# RP2350.net
KiCad netlist of a schematic drawn in Altium Designer
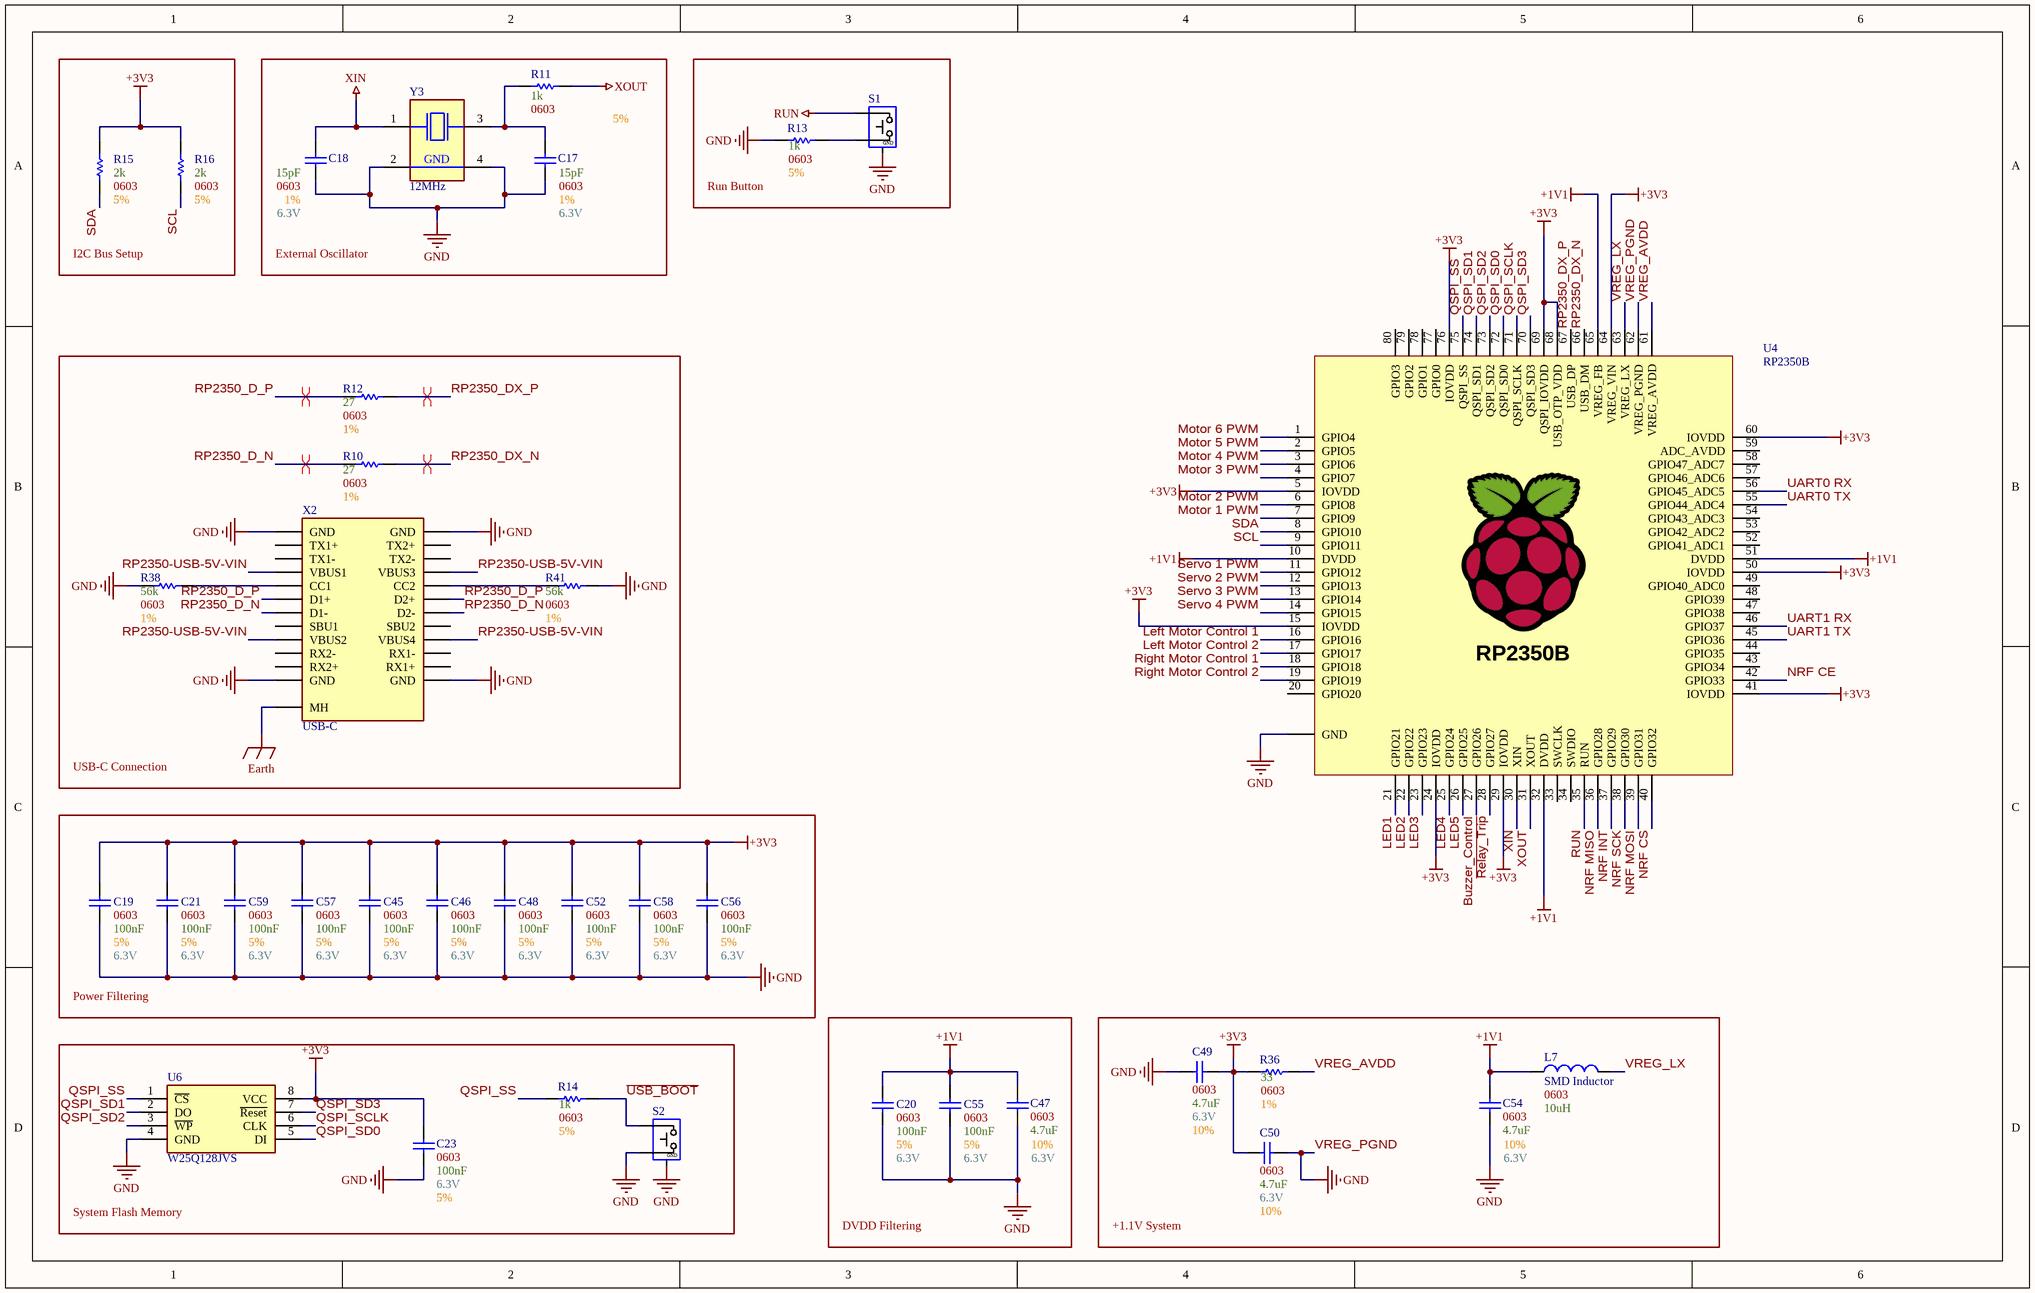
[diagram p0: RP2350.SchDoc]

(export (version "E")
  (design (tool "Eeschema 10.0.6"))
  (components
    (comp (ref "C17")
      (value "[Cap] SMD Nonpolarized")
      (footprint "[Cap] SMD 0603")
      (fields
        (field (name "SIZE PACKAGE") "0603")
        (field (name "CAPACITANCE") "15pF")
        (field (name "VOLTAGE") "6.3V")
        (field (name "TOLERANCE") "1%")
      )
      (libsource (lib "RADM Components") (part "[Cap] SMD Nonpolarized"))
    )
    (comp (ref "C18")
      (value "[Cap] SMD Nonpolarized")
      (footprint "[Cap] SMD 0603")
      (fields
        (field (name "SIZE PACKAGE") "0603")
        (field (name "CAPACITANCE") "15pF")
        (field (name "VOLTAGE") "6.3V")
        (field (name "TOLERANCE") "1%")
      )
      (libsource (lib "RADM Components") (part "[Cap] SMD Nonpolarized"))
    )
    (comp (ref "C19")
      (value "[Cap] SMD Nonpolarized")
      (footprint "[Cap] SMD 0603")
      (fields
        (field (name "SIZE PACKAGE") "0603")
        (field (name "CAPACITANCE") "100nF")
        (field (name "VOLTAGE") "6.3V")
        (field (name "TOLERANCE") "5%")
      )
      (libsource (lib "RADM Components") (part "[Cap] SMD Nonpolarized"))
    )
    (comp (ref "C20")
      (value "[Cap] SMD Nonpolarized")
      (footprint "[Cap] SMD 0603")
      (fields
        (field (name "SIZE PACKAGE") "0603")
        (field (name "CAPACITANCE") "100nF")
        (field (name "VOLTAGE") "6.3V")
        (field (name "TOLERANCE") "5%")
      )
      (libsource (lib "RADM Components") (part "[Cap] SMD Nonpolarized"))
    )
    (comp (ref "C21")
      (value "[Cap] SMD Nonpolarized")
      (footprint "[Cap] SMD 0603")
      (fields
        (field (name "SIZE PACKAGE") "0603")
        (field (name "CAPACITANCE") "100nF")
        (field (name "VOLTAGE") "6.3V")
        (field (name "TOLERANCE") "5%")
      )
      (libsource (lib "RADM Components") (part "[Cap] SMD Nonpolarized"))
    )
    (comp (ref "C23")
      (value "[Cap] SMD Nonpolarized")
      (footprint "[Cap] SMD 0603")
      (fields
        (field (name "SIZE PACKAGE") "0603")
        (field (name "CAPACITANCE") "100nF")
        (field (name "VOLTAGE") "6.3V")
        (field (name "TOLERANCE") "5%")
      )
      (libsource (lib "RADM Components") (part "[Cap] SMD Nonpolarized"))
    )
    (comp (ref "C45")
      (value "[Cap] SMD Nonpolarized")
      (footprint "[Cap] SMD 0603")
      (fields
        (field (name "SIZE PACKAGE") "0603")
        (field (name "CAPACITANCE") "100nF")
        (field (name "VOLTAGE") "6.3V")
        (field (name "TOLERANCE") "5%")
      )
      (libsource (lib "RADM Components") (part "[Cap] SMD Nonpolarized"))
    )
    (comp (ref "C46")
      (value "[Cap] SMD Nonpolarized")
      (footprint "[Cap] SMD 0603")
      (fields
        (field (name "SIZE PACKAGE") "0603")
        (field (name "CAPACITANCE") "100nF")
        (field (name "VOLTAGE") "6.3V")
        (field (name "TOLERANCE") "5%")
      )
      (libsource (lib "RADM Components") (part "[Cap] SMD Nonpolarized"))
    )
    (comp (ref "C47")
      (value "[Cap] SMD Nonpolarized")
      (footprint "[Cap] SMD 0603")
      (fields
        (field (name "SIZE PACKAGE") "0603")
        (field (name "CAPACITANCE") "4.7uF")
        (field (name "VOLTAGE") "6.3V")
        (field (name "TOLERANCE") "10%")
      )
      (libsource (lib "RADM Components") (part "[Cap] SMD Nonpolarized"))
    )
    (comp (ref "C48")
      (value "[Cap] SMD Nonpolarized")
      (footprint "[Cap] SMD 0603")
      (fields
        (field (name "SIZE PACKAGE") "0603")
        (field (name "CAPACITANCE") "100nF")
        (field (name "VOLTAGE") "6.3V")
        (field (name "TOLERANCE") "5%")
      )
      (libsource (lib "RADM Components") (part "[Cap] SMD Nonpolarized"))
    )
    (comp (ref "C49")
      (value "[Cap] SMD Nonpolarized")
      (footprint "[Cap] SMD 0603")
      (fields
        (field (name "SIZE PACKAGE") "0603")
        (field (name "CAPACITANCE") "4.7uF")
        (field (name "VOLTAGE") "6.3V")
        (field (name "TOLERANCE") "10%")
      )
      (libsource (lib "RADM Components") (part "[Cap] SMD Nonpolarized"))
    )
    (comp (ref "C50")
      (value "[Cap] SMD Nonpolarized")
      (footprint "[Cap] SMD 0603")
      (fields
        (field (name "SIZE PACKAGE") "0603")
        (field (name "CAPACITANCE") "4.7uF")
        (field (name "VOLTAGE") "6.3V")
        (field (name "TOLERANCE") "10%")
      )
      (libsource (lib "RADM Components") (part "[Cap] SMD Nonpolarized"))
    )
    (comp (ref "C52")
      (value "[Cap] SMD Nonpolarized")
      (footprint "[Cap] SMD 0603")
      (fields
        (field (name "SIZE PACKAGE") "0603")
        (field (name "CAPACITANCE") "100nF")
        (field (name "VOLTAGE") "6.3V")
        (field (name "TOLERANCE") "5%")
      )
      (libsource (lib "RADM Components") (part "[Cap] SMD Nonpolarized"))
    )
    (comp (ref "C54")
      (value "[Cap] SMD Nonpolarized")
      (footprint "[Cap] SMD 0603")
      (fields
        (field (name "SIZE PACKAGE") "0603")
        (field (name "CAPACITANCE") "4.7uF")
        (field (name "VOLTAGE") "6.3V")
        (field (name "TOLERANCE") "10%")
      )
      (libsource (lib "RADM Components") (part "[Cap] SMD Nonpolarized"))
    )
    (comp (ref "C55")
      (value "[Cap] SMD Nonpolarized")
      (footprint "[Cap] SMD 0603")
      (fields
        (field (name "SIZE PACKAGE") "0603")
        (field (name "CAPACITANCE") "100nF")
        (field (name "VOLTAGE") "6.3V")
        (field (name "TOLERANCE") "5%")
      )
      (libsource (lib "RADM Components") (part "[Cap] SMD Nonpolarized"))
    )
    (comp (ref "C56")
      (value "[Cap] SMD Nonpolarized")
      (footprint "[Cap] SMD 0603")
      (fields
        (field (name "SIZE PACKAGE") "0603")
        (field (name "CAPACITANCE") "100nF")
        (field (name "VOLTAGE") "6.3V")
        (field (name "TOLERANCE") "5%")
      )
      (libsource (lib "RADM Components") (part "[Cap] SMD Nonpolarized"))
    )
    (comp (ref "C57")
      (value "[Cap] SMD Nonpolarized")
      (footprint "[Cap] SMD 0603")
      (fields
        (field (name "SIZE PACKAGE") "0603")
        (field (name "CAPACITANCE") "100nF")
        (field (name "VOLTAGE") "6.3V")
        (field (name "TOLERANCE") "5%")
      )
      (libsource (lib "RADM Components") (part "[Cap] SMD Nonpolarized"))
    )
    (comp (ref "C58")
      (value "[Cap] SMD Nonpolarized")
      (footprint "[Cap] SMD 0603")
      (fields
        (field (name "SIZE PACKAGE") "0603")
        (field (name "CAPACITANCE") "100nF")
        (field (name "VOLTAGE") "6.3V")
        (field (name "TOLERANCE") "5%")
      )
      (libsource (lib "RADM Components") (part "[Cap] SMD Nonpolarized"))
    )
    (comp (ref "C59")
      (value "[Cap] SMD Nonpolarized")
      (footprint "[Cap] SMD 0603")
      (fields
        (field (name "SIZE PACKAGE") "0603")
        (field (name "CAPACITANCE") "100nF")
        (field (name "VOLTAGE") "6.3V")
        (field (name "TOLERANCE") "5%")
      )
      (libsource (lib "RADM Components") (part "[Cap] SMD Nonpolarized"))
    )
    (comp (ref "L7")
      (value "SMD Inductor")
      (footprint "[Inductor] SMD 0603")
      (fields (field (name "SIZE PACKAGE") "0603") (field (name "INDUCTANCE") "10uH"))
      (libsource (lib "RADM Components") (part "[Inductor] SMD Inductor"))
    )
    (comp (ref "R10")
      (value "[Res] SMD Resistor")
      (footprint "[Res] SMD 0603")
      (description "Generic")
      (fields
        (field (name "TOLERANCE") "1%")
        (field (name "RESISTANCE") "27")
        (field (name "SIZE PACKAGE") "0603")
      )
      (libsource (lib "RADM Components") (part "[Res] SMD Resistor"))
    )
    (comp (ref "R11")
      (value "[Res] SMD Resistor")
      (footprint "[Res] SMD 0603")
      (description "Generic")
      (fields
        (field (name "RESISTANCE") "1k")
        (field (name "SIZE PACKAGE") "0603")
        (field (name "TOLERANCE") "5%")
      )
      (libsource (lib "RADM Components") (part "[Res] SMD Resistor"))
    )
    (comp (ref "R12")
      (value "[Res] SMD Resistor")
      (footprint "[Res] SMD 0603")
      (description "Generic")
      (fields
        (field (name "TOLERANCE") "1%")
        (field (name "RESISTANCE") "27")
        (field (name "SIZE PACKAGE") "0603")
      )
      (libsource (lib "RADM Components") (part "[Res] SMD Resistor"))
    )
    (comp (ref "R13")
      (value "[Res] SMD Resistor")
      (footprint "[Res] SMD 0603")
      (description "Generic")
      (fields
        (field (name "RESISTANCE") "1k")
        (field (name "SIZE PACKAGE") "0603")
        (field (name "TOLERANCE") "5%")
      )
      (libsource (lib "RADM Components") (part "[Res] SMD Resistor"))
    )
    (comp (ref "R14")
      (value "[Res] SMD Resistor")
      (footprint "[Res] SMD 0603")
      (description "Generic")
      (fields
        (field (name "RESISTANCE") "1k")
        (field (name "SIZE PACKAGE") "0603")
        (field (name "TOLERANCE") "5%")
      )
      (libsource (lib "RADM Components") (part "[Res] SMD Resistor"))
    )
    (comp (ref "R15")
      (value "[Res] SMD Resistor")
      (footprint "[Res] SMD 0603")
      (description "Generic")
      (fields
        (field (name "RESISTANCE") "2k")
        (field (name "SIZE PACKAGE") "0603")
        (field (name "TOLERANCE") "5%")
      )
      (libsource (lib "RADM Components") (part "[Res] SMD Resistor"))
    )
    (comp (ref "R16")
      (value "[Res] SMD Resistor")
      (footprint "[Res] SMD 0603")
      (description "Generic")
      (fields
        (field (name "RESISTANCE") "2k")
        (field (name "SIZE PACKAGE") "0603")
        (field (name "TOLERANCE") "5%")
      )
      (libsource (lib "RADM Components") (part "[Res] SMD Resistor"))
    )
    (comp (ref "R36")
      (value "[Res] SMD Resistor")
      (footprint "[Res] SMD 0603")
      (description "Generic")
      (fields
        (field (name "RESISTANCE") "33")
        (field (name "SIZE PACKAGE") "0603")
        (field (name "TOLERANCE") "1%")
      )
      (libsource (lib "RADM Components") (part "[Res] SMD Resistor"))
    )
    (comp (ref "R38")
      (value "[Res] SMD Resistor")
      (footprint "[Res] SMD 0603")
      (description "Generic")
      (fields
        (field (name "TOLERANCE") "1%")
        (field (name "RESISTANCE") "56k")
        (field (name "SIZE PACKAGE") "0603")
      )
      (libsource (lib "RADM Components") (part "[Res] SMD Resistor"))
    )
    (comp (ref "R41")
      (value "[Res] SMD Resistor")
      (footprint "[Res] SMD 0603")
      (description "Generic")
      (fields
        (field (name "TOLERANCE") "1%")
        (field (name "RESISTANCE") "56k")
        (field (name "SIZE PACKAGE") "0603")
      )
      (libsource (lib "RADM Components") (part "[Res] SMD Resistor"))
    )
    (comp (ref "S1")
      (value "[Switch] Pushbutton SMD")
      (footprint "[Switch] Pushbutton SMD 2")
      (libsource (lib "RADM Components") (part "[Switch] Pushbutton SMD"))
    )
    (comp (ref "S2")
      (value "[Switch] Pushbutton SMD")
      (footprint "[Switch] Pushbutton SMD 2")
      (libsource (lib "RADM Components") (part "[Switch] Pushbutton SMD"))
    )
    (comp (ref "U4")
      (value "RP2350B")
      (footprint "[MCU] RP2350B")
      (description "QFN-80 Package")
      (libsource (lib "RADM Components") (part "[MCU] RP2350B"))
    )
    (comp (ref "U6")
      (value "W25Q128JVS")
      (footprint "[Mem] 16Mb Flash Memory")
      (description "W25Q128JVSIQ TR")
      (libsource (lib "RADM Components") (part "[Mem] 16Mb Flash Memory"))
    )
    (comp (ref "X2")
      (value "USB-C")
      (footprint "[Port] USB-C")
      (libsource (lib "RADM Connectors") (part "[Port] USB Type-C"))
    )
    (comp (ref "Y3")
      (value "12MHz")
      (footprint "[XTAL] SMD 12MHz")
      (description "815-ABM8-272-T3")
      (libsource (lib "RADM Components") (part "[XTAL] SMD 12MHz"))
    )
  )
  (nets
    (net (code "1") (name "+1V1") (class "Default")
      (node (ref "C20") (pin "2") (pinfunction "2_2") (pintype "passive"))
      (node (ref "C47") (pin "2") (pinfunction "2_2") (pintype "passive"))
      (node (ref "C54") (pin "2") (pinfunction "2_2") (pintype "passive"))
      (node (ref "C55") (pin "2") (pinfunction "2_2") (pintype "passive"))
      (node (ref "L7") (pin "1") (pinfunction "1_1") (pintype "passive"))
      (node (ref "U4") (pin "10") (pinfunction "DVDD_10") (pintype "passive"))
      (node (ref "U4") (pin "32") (pinfunction "DVDD_32") (pintype "passive"))
      (node (ref "U4") (pin "51") (pinfunction "DVDD_51") (pintype "passive"))
      (node (ref "U4") (pin "65") (pinfunction "VREG_FB_65") (pintype "passive"))
    )
    (net (code "2") (name "+3V3") (class "Default")
      (node (ref "C19") (pin "2") (pinfunction "2_2") (pintype "passive"))
      (node (ref "C21") (pin "2") (pinfunction "2_2") (pintype "passive"))
      (node (ref "C23") (pin "1") (pinfunction "1_1") (pintype "passive"))
      (node (ref "C45") (pin "2") (pinfunction "2_2") (pintype "passive"))
      (node (ref "C46") (pin "2") (pinfunction "2_2") (pintype "passive"))
      (node (ref "C48") (pin "2") (pinfunction "2_2") (pintype "passive"))
      (node (ref "C49") (pin "1") (pinfunction "1_1") (pintype "passive"))
      (node (ref "C50") (pin "2") (pinfunction "2_2") (pintype "passive"))
      (node (ref "C52") (pin "2") (pinfunction "2_2") (pintype "passive"))
      (node (ref "C56") (pin "2") (pinfunction "2_2") (pintype "passive"))
      (node (ref "C57") (pin "2") (pinfunction "2_2") (pintype "passive"))
      (node (ref "C58") (pin "2") (pinfunction "2_2") (pintype "passive"))
      (node (ref "C59") (pin "2") (pinfunction "2_2") (pintype "passive"))
      (node (ref "R15") (pin "2") (pinfunction "2_2") (pintype "passive"))
      (node (ref "R16") (pin "2") (pinfunction "2_2") (pintype "passive"))
      (node (ref "R36") (pin "2") (pinfunction "2_2") (pintype "passive"))
      (node (ref "U4") (pin "15") (pinfunction "IOVDD_15") (pintype "passive"))
      (node (ref "U4") (pin "24") (pinfunction "IOVDD_24") (pintype "passive"))
      (node (ref "U4") (pin "29") (pinfunction "IOVDD_29") (pintype "passive"))
      (node (ref "U4") (pin "41") (pinfunction "IOVDD_41") (pintype "passive"))
      (node (ref "U4") (pin "5") (pinfunction "IOVDD_5") (pintype "passive"))
      (node (ref "U4") (pin "50") (pinfunction "IOVDD_50") (pintype "passive"))
      (node (ref "U4") (pin "60") (pinfunction "IOVDD_60") (pintype "passive"))
      (node (ref "U4") (pin "64") (pinfunction "VREG_VIN_64") (pintype "passive"))
      (node (ref "U4") (pin "68") (pinfunction "USB_OTP_VDD_68") (pintype "passive"))
      (node (ref "U4") (pin "69") (pinfunction "QSPI_IOVDD_69") (pintype "passive"))
      (node (ref "U4") (pin "76") (pinfunction "IOVDD_76") (pintype "passive"))
      (node (ref "U6") (pin "8") (pinfunction "VCC_8") (pintype "passive"))
    )
    (net (code "3") (name "/Buzzer_Control") (class "Default")
      (node (ref "U4") (pin "27") (pinfunction "GPIO26_27") (pintype "passive"))
    )
    (net (code "4") (name "/LED1") (class "Default")
      (node (ref "U4") (pin "21") (pinfunction "GPIO21_21") (pintype "passive"))
    )
    (net (code "5") (name "/LED2") (class "Default")
      (node (ref "U4") (pin "22") (pinfunction "GPIO22_22") (pintype "passive"))
    )
    (net (code "6") (name "/LED3") (class "Default")
      (node (ref "U4") (pin "23") (pinfunction "GPIO23_23") (pintype "passive"))
    )
    (net (code "7") (name "/LED4") (class "Default")
      (node (ref "U4") (pin "25") (pinfunction "GPIO24_25") (pintype "passive"))
    )
    (net (code "8") (name "/LED5") (class "Default")
      (node (ref "U4") (pin "26") (pinfunction "GPIO25_26") (pintype "passive"))
    )
    (net (code "9") (name "/Left Motor Control 1") (class "Default")
      (node (ref "U4") (pin "16") (pinfunction "GPIO16_16") (pintype "passive"))
    )
    (net (code "10") (name "/Left Motor Control 2") (class "Default")
      (node (ref "U4") (pin "17") (pinfunction "GPIO17_17") (pintype "passive"))
    )
    (net (code "11") (name "/Motor 1 PWM") (class "Default")
      (node (ref "U4") (pin "7") (pinfunction "GPIO9_7") (pintype "passive"))
    )
    (net (code "12") (name "/Motor 2 PWM") (class "Default")
      (node (ref "U4") (pin "6") (pinfunction "GPIO8_6") (pintype "passive"))
    )
    (net (code "13") (name "/Motor 3 PWM") (class "Default")
      (node (ref "U4") (pin "4") (pinfunction "GPIO7_4") (pintype "passive"))
    )
    (net (code "14") (name "/Motor 4 PWM") (class "Default")
      (node (ref "U4") (pin "3") (pinfunction "GPIO6_3") (pintype "passive"))
    )
    (net (code "15") (name "/Motor 5 PWM") (class "Default")
      (node (ref "U4") (pin "2") (pinfunction "GPIO5_2") (pintype "passive"))
    )
    (net (code "16") (name "/Motor 6 PWM") (class "Default")
      (node (ref "U4") (pin "1") (pinfunction "GPIO4_1") (pintype "passive"))
    )
    (net (code "17") (name "/NRF CE") (class "Default")
      (node (ref "U4") (pin "42") (pinfunction "GPIO33_42") (pintype "passive"))
    )
    (net (code "18") (name "/NRF CS") (class "Default")
      (node (ref "U4") (pin "40") (pinfunction "GPIO32_40") (pintype "passive"))
    )
    (net (code "19") (name "/NRF INT") (class "Default")
      (node (ref "U4") (pin "37") (pinfunction "GPIO29_37") (pintype "passive"))
    )
    (net (code "20") (name "/NRF MISO") (class "Default")
      (node (ref "U4") (pin "36") (pinfunction "GPIO28_36") (pintype "passive"))
    )
    (net (code "21") (name "/NRF MOSI") (class "Default")
      (node (ref "U4") (pin "39") (pinfunction "GPIO31_39") (pintype "passive"))
    )
    (net (code "22") (name "/NRF SCK") (class "Default")
      (node (ref "U4") (pin "38") (pinfunction "GPIO30_38") (pintype "passive"))
    )
    (net (code "23") (name "/QSPI_SCLK") (class "Default")
      (node (ref "U4") (pin "71") (pinfunction "QSPI_SCLK_71") (pintype "passive"))
      (node (ref "U6") (pin "6") (pinfunction "CLK_6") (pintype "passive"))
    )
    (net (code "24") (name "/QSPI_SD0") (class "Default")
      (node (ref "U4") (pin "72") (pinfunction "QSPI_SD0_72") (pintype "passive"))
      (node (ref "U6") (pin "5") (pinfunction "DI_5") (pintype "passive"))
    )
    (net (code "25") (name "/QSPI_SD1") (class "Default")
      (node (ref "U4") (pin "74") (pinfunction "QSPI_SD1_74") (pintype "passive"))
      (node (ref "U6") (pin "2") (pinfunction "DO_2") (pintype "passive"))
    )
    (net (code "26") (name "/QSPI_SD2") (class "Default")
      (node (ref "U4") (pin "73") (pinfunction "QSPI_SD2_73") (pintype "passive"))
      (node (ref "U6") (pin "3") (pinfunction "~{WP}_3") (pintype "passive"))
    )
    (net (code "27") (name "/QSPI_SD3") (class "Default")
      (node (ref "U4") (pin "70") (pinfunction "QSPI_SD3_70") (pintype "passive"))
      (node (ref "U6") (pin "7") (pinfunction "~{Reset}_7") (pintype "passive"))
    )
    (net (code "28") (name "/QSPI_SS") (class "Default")
      (node (ref "R14") (pin "2") (pinfunction "2_2") (pintype "passive"))
      (node (ref "U4") (pin "75") (pinfunction "QSPI_SS_75") (pintype "passive"))
      (node (ref "U6") (pin "1") (pinfunction "~{CS}_1") (pintype "passive"))
    )
    (net (code "29") (name "/RP2350-USB-5V-VIN") (class "Default")
      (node (ref "X2") (pin "A4") (pinfunction "VBUS1_A4") (pintype "passive"))
      (node (ref "X2") (pin "A9") (pinfunction "VBUS2_A9") (pintype "passive"))
      (node (ref "X2") (pin "B4") (pinfunction "VBUS3_B4") (pintype "passive"))
      (node (ref "X2") (pin "B9") (pinfunction "VBUS4_B9") (pintype "passive"))
    )
    (net (code "30") (name "/RP2350_DX_N") (class "Default")
      (node (ref "R10") (pin "2") (pinfunction "2_2") (pintype "passive"))
      (node (ref "U4") (pin "66") (pinfunction "USB_DM_66") (pintype "passive"))
    )
    (net (code "31") (name "/RP2350_DX_P") (class "Default")
      (node (ref "R12") (pin "2") (pinfunction "2_2") (pintype "passive"))
      (node (ref "U4") (pin "67") (pinfunction "USB_DP_67") (pintype "passive"))
    )
    (net (code "32") (name "/RP2350_D_N") (class "Default")
      (node (ref "R10") (pin "1") (pinfunction "1_1") (pintype "passive"))
      (node (ref "X2") (pin "A7") (pinfunction "D1-_A7") (pintype "passive"))
      (node (ref "X2") (pin "B7") (pinfunction "D2-_B7") (pintype "passive"))
    )
    (net (code "33") (name "/RP2350_D_P") (class "Default")
      (node (ref "R12") (pin "1") (pinfunction "1_1") (pintype "passive"))
      (node (ref "X2") (pin "A6") (pinfunction "D1+_A6") (pintype "passive"))
      (node (ref "X2") (pin "B6") (pinfunction "D2+_B6") (pintype "passive"))
    )
    (net (code "34") (name "/Relay_Trip") (class "Default")
      (node (ref "U4") (pin "28") (pinfunction "GPIO27_28") (pintype "passive"))
    )
    (net (code "35") (name "/Right Motor Control 1") (class "Default")
      (node (ref "U4") (pin "18") (pinfunction "GPIO18_18") (pintype "passive"))
    )
    (net (code "36") (name "/Right Motor Control 2") (class "Default")
      (node (ref "U4") (pin "19") (pinfunction "GPIO19_19") (pintype "passive"))
    )
    (net (code "37") (name "/SCL") (class "Default")
      (node (ref "R16") (pin "1") (pinfunction "1_1") (pintype "passive"))
      (node (ref "U4") (pin "9") (pinfunction "GPIO11_9") (pintype "passive"))
    )
    (net (code "38") (name "/SDA") (class "Default")
      (node (ref "R15") (pin "1") (pinfunction "1_1") (pintype "passive"))
      (node (ref "U4") (pin "8") (pinfunction "GPIO10_8") (pintype "passive"))
    )
    (net (code "39") (name "/Servo 1 PWM") (class "Default")
      (node (ref "U4") (pin "11") (pinfunction "GPIO12_11") (pintype "passive"))
    )
    (net (code "40") (name "/Servo 2 PWM") (class "Default")
      (node (ref "U4") (pin "12") (pinfunction "GPIO13_12") (pintype "passive"))
    )
    (net (code "41") (name "/Servo 3 PWM") (class "Default")
      (node (ref "U4") (pin "13") (pinfunction "GPIO14_13") (pintype "passive"))
    )
    (net (code "42") (name "/Servo 4 PWM") (class "Default")
      (node (ref "U4") (pin "14") (pinfunction "GPIO15_14") (pintype "passive"))
    )
    (net (code "43") (name "/UART0 RX") (class "Default")
      (node (ref "U4") (pin "56") (pinfunction "GPIO45_ADC5_56") (pintype "passive"))
    )
    (net (code "44") (name "/UART0 TX") (class "Default")
      (node (ref "U4") (pin "55") (pinfunction "GPIO44_ADC4_55") (pintype "passive"))
    )
    (net (code "45") (name "/UART1 RX") (class "Default")
      (node (ref "U4") (pin "46") (pinfunction "GPIO37_46") (pintype "passive"))
    )
    (net (code "46") (name "/UART1 TX") (class "Default")
      (node (ref "U4") (pin "45") (pinfunction "GPIO36_45") (pintype "passive"))
    )
    (net (code "47") (name "/VREG_AVDD") (class "Default")
      (node (ref "R36") (pin "1") (pinfunction "1_1") (pintype "passive"))
      (node (ref "U4") (pin "61") (pinfunction "VREG_AVDD_61") (pintype "passive"))
    )
    (net (code "48") (name "/VREG_LX") (class "Default")
      (node (ref "L7") (pin "2") (pinfunction "2_2") (pintype "passive"))
      (node (ref "U4") (pin "63") (pinfunction "VREG_LX_63") (pintype "passive"))
    )
    (net (code "49") (name "/~{USB_BOOT}") (class "Default")
      (node (ref "R14") (pin "1") (pinfunction "1_1") (pintype "passive"))
      (node (ref "S2") (pin "1") (pintype "power_in"))
    )
    (net (code "50") (name "Earth") (class "Default")
      (node (ref "X2") (pin "MH") (pinfunction "MH_MH") (pintype "passive"))
    )
    (net (code "51") (name "GND") (class "Default")
      (node (ref "C17") (pin "1") (pinfunction "1_1") (pintype "passive"))
      (node (ref "C18") (pin "1") (pinfunction "1_1") (pintype "passive"))
      (node (ref "C19") (pin "1") (pinfunction "1_1") (pintype "passive"))
      (node (ref "C20") (pin "1") (pinfunction "1_1") (pintype "passive"))
      (node (ref "C21") (pin "1") (pinfunction "1_1") (pintype "passive"))
      (node (ref "C23") (pin "2") (pinfunction "2_2") (pintype "passive"))
      (node (ref "C45") (pin "1") (pinfunction "1_1") (pintype "passive"))
      (node (ref "C46") (pin "1") (pinfunction "1_1") (pintype "passive"))
      (node (ref "C47") (pin "1") (pinfunction "1_1") (pintype "passive"))
      (node (ref "C48") (pin "1") (pinfunction "1_1") (pintype "passive"))
      (node (ref "C49") (pin "2") (pinfunction "2_2") (pintype "passive"))
      (node (ref "C50") (pin "1") (pinfunction "1_1") (pintype "passive"))
      (node (ref "C52") (pin "1") (pinfunction "1_1") (pintype "passive"))
      (node (ref "C54") (pin "1") (pinfunction "1_1") (pintype "passive"))
      (node (ref "C55") (pin "1") (pinfunction "1_1") (pintype "passive"))
      (node (ref "C56") (pin "1") (pinfunction "1_1") (pintype "passive"))
      (node (ref "C57") (pin "1") (pinfunction "1_1") (pintype "passive"))
      (node (ref "C58") (pin "1") (pinfunction "1_1") (pintype "passive"))
      (node (ref "C59") (pin "1") (pinfunction "1_1") (pintype "passive"))
      (node (ref "R13") (pin "2") (pinfunction "2_2") (pintype "passive"))
      (node (ref "R38") (pin "1") (pinfunction "1_1") (pintype "passive"))
      (node (ref "R41") (pin "2") (pinfunction "2_2") (pintype "passive"))
      (node (ref "S1") (pin "GND") (pinfunction "GND_GND") (pintype "power_in"))
      (node (ref "S2") (pin "2") (pintype "power_in"))
      (node (ref "S2") (pin "GND") (pinfunction "GND_GND") (pintype "power_in"))
      (node (ref "U4") (pin "62") (pinfunction "VREG_PGND_62") (pintype "passive"))
      (node (ref "U4") (pin "Pad") (pinfunction "GND_Pad") (pintype "passive"))
      (node (ref "U6") (pin "4") (pinfunction "GND_4") (pintype "passive"))
      (node (ref "X2") (pin "A1") (pinfunction "GND_A1") (pintype "passive"))
      (node (ref "X2") (pin "A12") (pinfunction "GND_A12") (pintype "passive"))
      (node (ref "X2") (pin "B1") (pinfunction "GND_B1") (pintype "passive"))
      (node (ref "X2") (pin "B12") (pinfunction "GND_B12") (pintype "passive"))
      (node (ref "Y3") (pin "2") (pinfunction "GND_2") (pintype "power_in"))
      (node (ref "Y3") (pin "4") (pinfunction "GND_4") (pintype "power_in"))
    )
    (net (code "52") (name "Net-(R13-Pad1)") (class "Default")
      (node (ref "R13") (pin "1") (pinfunction "1_1") (pintype "passive"))
      (node (ref "S1") (pin "2") (pintype "power_in"))
    )
    (net (code "53") (name "Net-(X2-CC1)") (class "Default")
      (node (ref "R38") (pin "2") (pinfunction "2_2") (pintype "passive"))
      (node (ref "X2") (pin "A5") (pinfunction "CC1_A5") (pintype "passive"))
    )
    (net (code "54") (name "Net-(X2-CC2)") (class "Default")
      (node (ref "R41") (pin "1") (pinfunction "1_1") (pintype "passive"))
      (node (ref "X2") (pin "B5") (pinfunction "CC2_B5") (pintype "passive"))
    )
    (net (code "55") (name "Net-(Y3-XTAL2)") (class "Default")
      (node (ref "C17") (pin "2") (pinfunction "2_2") (pintype "passive"))
      (node (ref "R11") (pin "2") (pinfunction "2_2") (pintype "passive"))
      (node (ref "Y3") (pin "3") (pinfunction "XTAL2_3") (pintype "power_in"))
    )
    (net (code "56") (name "RUN") (class "Default")
      (node (ref "S1") (pin "1") (pintype "power_in"))
      (node (ref "U4") (pin "35") (pinfunction "RUN_35") (pintype "passive"))
    )
    (net (code "57") (name "XIN") (class "Default")
      (node (ref "C18") (pin "2") (pinfunction "2_2") (pintype "passive"))
      (node (ref "U4") (pin "30") (pinfunction "XIN_30") (pintype "passive"))
      (node (ref "Y3") (pin "1") (pinfunction "XTAL1_1") (pintype "power_in"))
    )
    (net (code "58") (name "XOUT") (class "Default")
      (node (ref "R11") (pin "1") (pinfunction "1_1") (pintype "passive"))
      (node (ref "U4") (pin "31") (pinfunction "XOUT_31") (pintype "passive"))
    )
    (net (code "59") (name "unconnected-(U4-ADC_AVDD-Pad59)") (class "Default")
      (node (ref "U4") (pin "59") (pinfunction "ADC_AVDD_59") (pintype "passive"))
    )
    (net (code "60") (name "unconnected-(U4-GPIO0-Pad77)") (class "Default")
      (node (ref "U4") (pin "77") (pinfunction "GPIO0_77") (pintype "passive"))
    )
    (net (code "61") (name "unconnected-(U4-GPIO1-Pad78)") (class "Default")
      (node (ref "U4") (pin "78") (pinfunction "GPIO1_78") (pintype "passive"))
    )
    (net (code "62") (name "unconnected-(U4-GPIO2-Pad79)") (class "Default")
      (node (ref "U4") (pin "79") (pinfunction "GPIO2_79") (pintype "passive"))
    )
    (net (code "63") (name "unconnected-(U4-GPIO3-Pad80)") (class "Default")
      (node (ref "U4") (pin "80") (pinfunction "GPIO3_80") (pintype "passive"))
    )
    (net (code "64") (name "unconnected-(U4-GPIO20-Pad20)") (class "Default")
      (node (ref "U4") (pin "20") (pinfunction "GPIO20_20") (pintype "passive"))
    )
    (net (code "65") (name "unconnected-(U4-GPIO34-Pad43)") (class "Default")
      (node (ref "U4") (pin "43") (pinfunction "GPIO34_43") (pintype "passive"))
    )
    (net (code "66") (name "unconnected-(U4-GPIO35-Pad44)") (class "Default")
      (node (ref "U4") (pin "44") (pinfunction "GPIO35_44") (pintype "passive"))
    )
    (net (code "67") (name "unconnected-(U4-GPIO38-Pad47)") (class "Default")
      (node (ref "U4") (pin "47") (pinfunction "GPIO38_47") (pintype "passive"))
    )
    (net (code "68") (name "unconnected-(U4-GPIO39-Pad48)") (class "Default")
      (node (ref "U4") (pin "48") (pinfunction "GPIO39_48") (pintype "passive"))
    )
    (net (code "69") (name "unconnected-(U4-GPIO40_ADC0-Pad49)") (class "Default")
      (node (ref "U4") (pin "49") (pinfunction "GPIO40_ADC0_49") (pintype "passive"))
    )
    (net (code "70") (name "unconnected-(U4-GPIO41_ADC1-Pad52)") (class "Default")
      (node (ref "U4") (pin "52") (pinfunction "GPIO41_ADC1_52") (pintype "passive"))
    )
    (net (code "71") (name "unconnected-(U4-GPIO42_ADC2-Pad53)") (class "Default")
      (node (ref "U4") (pin "53") (pinfunction "GPIO42_ADC2_53") (pintype "passive"))
    )
    (net (code "72") (name "unconnected-(U4-GPIO43_ADC3-Pad54)") (class "Default")
      (node (ref "U4") (pin "54") (pinfunction "GPIO43_ADC3_54") (pintype "passive"))
    )
    (net (code "73") (name "unconnected-(U4-GPIO46_ADC6-Pad57)") (class "Default")
      (node (ref "U4") (pin "57") (pinfunction "GPIO46_ADC6_57") (pintype "passive"))
    )
    (net (code "74") (name "unconnected-(U4-GPIO47_ADC7-Pad58)") (class "Default")
      (node (ref "U4") (pin "58") (pinfunction "GPIO47_ADC7_58") (pintype "passive"))
    )
    (net (code "75") (name "unconnected-(U4-SWCLK-Pad33)") (class "Default")
      (node (ref "U4") (pin "33") (pinfunction "SWCLK_33") (pintype "passive"))
    )
    (net (code "76") (name "unconnected-(U4-SWDIO-Pad34)") (class "Default")
      (node (ref "U4") (pin "34") (pinfunction "SWDIO_34") (pintype "passive"))
    )
    (net (code "77") (name "unconnected-(X2-RX1+-PadB11)") (class "Default")
      (node (ref "X2") (pin "B11") (pinfunction "RX1+_B11") (pintype "passive"))
    )
    (net (code "78") (name "unconnected-(X2-RX1--PadB10)") (class "Default")
      (node (ref "X2") (pin "B10") (pinfunction "RX1-_B10") (pintype "passive"))
    )
    (net (code "79") (name "unconnected-(X2-RX2+-PadA11)") (class "Default")
      (node (ref "X2") (pin "A11") (pinfunction "RX2+_A11") (pintype "passive"))
    )
    (net (code "80") (name "unconnected-(X2-RX2--PadA10)") (class "Default")
      (node (ref "X2") (pin "A10") (pinfunction "RX2-_A10") (pintype "passive"))
    )
    (net (code "81") (name "unconnected-(X2-SBU1-PadA8)") (class "Default")
      (node (ref "X2") (pin "A8") (pinfunction "SBU1_A8") (pintype "passive"))
    )
    (net (code "82") (name "unconnected-(X2-SBU2-PadB8)") (class "Default")
      (node (ref "X2") (pin "B8") (pinfunction "SBU2_B8") (pintype "passive"))
    )
    (net (code "83") (name "unconnected-(X2-TX1+-PadA2)") (class "Default")
      (node (ref "X2") (pin "A2") (pinfunction "TX1+_A2") (pintype "passive"))
    )
    (net (code "84") (name "unconnected-(X2-TX1--PadA3)") (class "Default")
      (node (ref "X2") (pin "A3") (pinfunction "TX1-_A3") (pintype "passive"))
    )
    (net (code "85") (name "unconnected-(X2-TX2+-PadB2)") (class "Default")
      (node (ref "X2") (pin "B2") (pinfunction "TX2+_B2") (pintype "passive"))
    )
    (net (code "86") (name "unconnected-(X2-TX2--PadB3)") (class "Default")
      (node (ref "X2") (pin "B3") (pinfunction "TX2-_B3") (pintype "passive"))
    )
  )
)
